# vFx-Teensy4_0.net
KiCad netlist of a schematic drawn in EAGLE
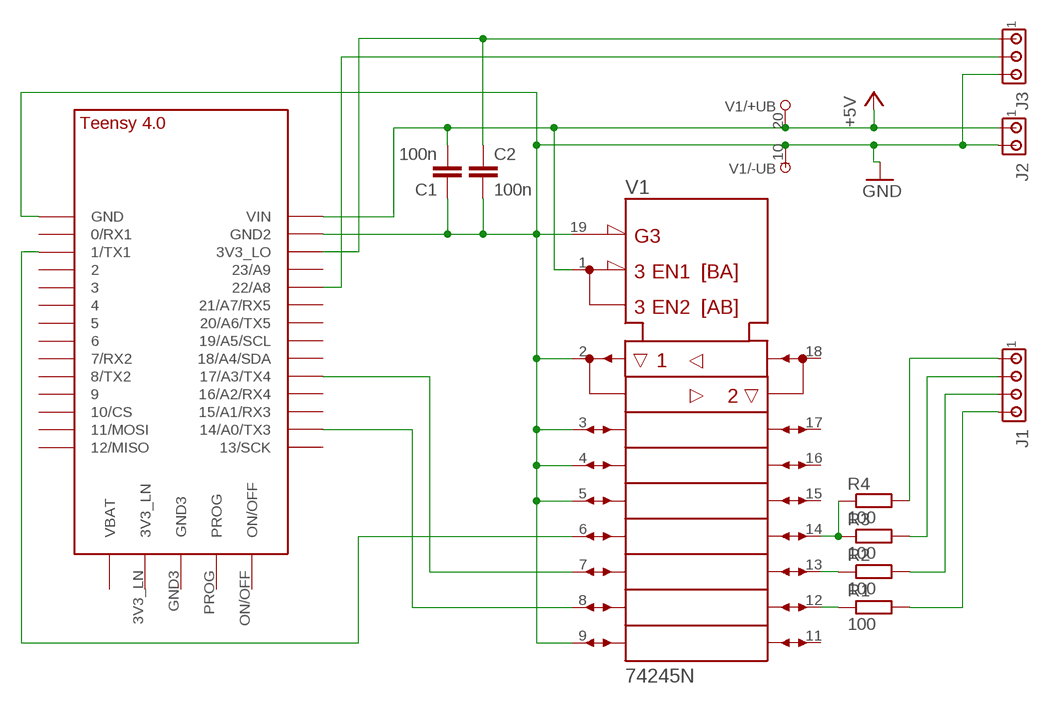
[diagram p0: schematic, sheet 1]

(export (version "E")
  (design (tool "Eeschema 10.0.6"))
  (components
    (comp (ref "C1")
      (value "100n")
      (footprint "eagle-import:C050-025X075")
      (libsource (lib "eagle-import") (part "C-EU050-025X075"))
    )
    (comp (ref "C2")
      (value "100n")
      (footprint "eagle-import:C050-025X075")
      (libsource (lib "eagle-import") (part "C-EU050-025X075"))
    )
    (comp (ref "J1")
      (value "MTA04-100")
      (footprint "eagle-import:10X04MTA")
      (libsource (lib "eagle-import") (part "MTA04-100"))
    )
    (comp (ref "J2")
      (value "MTA02-100")
      (footprint "eagle-import:10X02MTA")
      (libsource (lib "eagle-import") (part "MTA02-100"))
    )
    (comp (ref "J3")
      (value "MTA03-100")
      (footprint "eagle-import:10X03MTA")
      (libsource (lib "eagle-import") (part "MTA03-100"))
    )
    (comp (ref "R1")
      (value "100")
      (footprint "eagle-import:0207_10")
      (libsource (lib "eagle-import") (part "R-EU_0207/10"))
    )
    (comp (ref "R2")
      (value "100")
      (footprint "eagle-import:0207_10")
      (libsource (lib "eagle-import") (part "R-EU_0207/10"))
    )
    (comp (ref "R3")
      (value "100")
      (footprint "eagle-import:0207_10")
      (libsource (lib "eagle-import") (part "R-EU_0207/10"))
    )
    (comp (ref "R4")
      (value "100")
      (footprint "eagle-import:0207_10")
      (libsource (lib "eagle-import") (part "R-EU_0207/10"))
    )
    (comp (ref "U$1")
      (value "TEENSY_4.0-BASIC")
      (footprint "eagle-import:TEENSY_4.0-BASIC")
      (libsource (lib "eagle-import") (part "TEENSY_4.0-BASIC"))
    )
    (comp (ref "V1")
      (value "74245N")
      (footprint "eagle-import:DIL20")
      (libsource (lib "eagle-import") (part "74245N"))
    )
  )
  (nets
    (net (code "1") (name "+5V") (class "Default")
      (node (ref "C1") (pin "2") (pinfunction "2_2") (pintype "passive"))
      (node (ref "J2") (pin "1") (pinfunction "1_1") (pintype "passive"))
      (node (ref "U$1") (pin "VIN") (pinfunction "VIN_VIN") (pintype "bidirectional"))
      (node (ref "V1") (pin "1") (pinfunction "DIR_1") (pintype "input"))
      (node (ref "V1") (pin "20") (pinfunction "+UB_20") (pintype "power_in"))
    )
    (net (code "2") (name "GND") (class "Default")
      (node (ref "C1") (pin "1") (pinfunction "1_1") (pintype "passive"))
      (node (ref "C2") (pin "2") (pinfunction "2_2") (pintype "passive"))
      (node (ref "J2") (pin "2") (pinfunction "2_2") (pintype "passive"))
      (node (ref "J3") (pin "3") (pinfunction "3_3") (pintype "passive"))
      (node (ref "U$1") (pin "GND") (pinfunction "GND_GND") (pintype "bidirectional"))
      (node (ref "U$1") (pin "GND2") (pinfunction "GND2_GND2") (pintype "bidirectional"))
      (node (ref "V1") (pin "10") (pinfunction "-UB_10") (pintype "power_in"))
      (node (ref "V1") (pin "19") (pinfunction "~{G}_19") (pintype "input"))
      (node (ref "V1") (pin "2") (pinfunction "A1_2") (pintype "bidirectional"))
      (node (ref "V1") (pin "3") (pinfunction "A2_3") (pintype "bidirectional"))
      (node (ref "V1") (pin "4") (pinfunction "A3_4") (pintype "bidirectional"))
      (node (ref "V1") (pin "5") (pinfunction "A4_5") (pintype "bidirectional"))
      (node (ref "V1") (pin "9") (pinfunction "A8_9") (pintype "bidirectional"))
    )
    (net (code "3") (name "Net-(C2-Pad1)") (class "Default")
      (node (ref "C2") (pin "1") (pinfunction "1_1") (pintype "passive"))
      (node (ref "J3") (pin "1") (pinfunction "1_1") (pintype "passive"))
      (node (ref "U$1") (pin "3V3_LO") (pinfunction "3V3_LO_3V3_LO") (pintype "bidirectional"))
    )
    (net (code "4") (name "Net-(J1-Pad1)") (class "Default")
      (node (ref "J1") (pin "1") (pinfunction "1_1") (pintype "passive"))
      (node (ref "R4") (pin "2") (pinfunction "2_2") (pintype "passive"))
    )
    (net (code "5") (name "Net-(J1-Pad2)") (class "Default")
      (node (ref "J1") (pin "2") (pinfunction "2_2") (pintype "passive"))
      (node (ref "R3") (pin "2") (pinfunction "2_2") (pintype "passive"))
    )
    (net (code "6") (name "Net-(J1-Pad3)") (class "Default")
      (node (ref "J1") (pin "3") (pinfunction "3_3") (pintype "passive"))
      (node (ref "R2") (pin "2") (pinfunction "2_2") (pintype "passive"))
    )
    (net (code "7") (name "Net-(J1-Pad4)") (class "Default")
      (node (ref "J1") (pin "4") (pinfunction "4_4") (pintype "passive"))
      (node (ref "R1") (pin "2") (pinfunction "2_2") (pintype "passive"))
    )
    (net (code "8") (name "Net-(J3-Pad2)") (class "Default")
      (node (ref "J3") (pin "2") (pinfunction "2_2") (pintype "passive"))
      (node (ref "U$1") (pin "22/A8") (pinfunction "22/A8_22/A8") (pintype "bidirectional"))
    )
    (net (code "9") (name "Net-(U$1-1{slash}TX1)") (class "Default")
      (node (ref "U$1") (pin "1/TX") (pinfunction "1/TX1_1/TX") (pintype "bidirectional"))
      (node (ref "V1") (pin "6") (pinfunction "A5_6") (pintype "bidirectional"))
    )
    (net (code "10") (name "Net-(U$1-14{slash}A0{slash}TX3)") (class "Default")
      (node (ref "U$1") (pin "14/A0") (pinfunction "14/A0/TX3_14/A0") (pintype "bidirectional"))
      (node (ref "V1") (pin "8") (pinfunction "A7_8") (pintype "bidirectional"))
    )
    (net (code "11") (name "Net-(U$1-17{slash}A3{slash}TX4)") (class "Default")
      (node (ref "U$1") (pin "17/A3") (pinfunction "17/A3/TX4_17/A3") (pintype "bidirectional"))
      (node (ref "V1") (pin "7") (pinfunction "A6_7") (pintype "bidirectional"))
    )
    (net (code "12") (name "Net-(V1C-B5)") (class "Default")
      (node (ref "R3") (pin "1") (pinfunction "1_1") (pintype "passive"))
      (node (ref "R4") (pin "1") (pinfunction "1_1") (pintype "passive"))
      (node (ref "V1") (pin "14") (pinfunction "B5_14") (pintype "bidirectional"))
    )
    (net (code "13") (name "Net-(V1C-B6)") (class "Default")
      (node (ref "R2") (pin "1") (pinfunction "1_1") (pintype "passive"))
      (node (ref "V1") (pin "13") (pinfunction "B6_13") (pintype "bidirectional"))
    )
    (net (code "14") (name "Net-(V1C-B7)") (class "Default")
      (node (ref "R1") (pin "1") (pinfunction "1_1") (pintype "passive"))
      (node (ref "V1") (pin "12") (pinfunction "B7_12") (pintype "bidirectional"))
    )
    (net (code "15") (name "unconnected-(U$1-0{slash}RX1-Pad0{slash}RX)") (class "Default")
      (node (ref "U$1") (pin "0/RX") (pinfunction "0/RX1_0/RX") (pintype "bidirectional"))
    )
    (net (code "16") (name "unconnected-(U$1-3-Pad3{slash}CANTX)") (class "Default")
      (node (ref "U$1") (pin "3/CANTX") (pinfunction "3_3/CANTX") (pintype "bidirectional"))
    )
    (net (code "17") (name "unconnected-(U$1-4-Pad4{slash}CANRX)") (class "Default")
      (node (ref "U$1") (pin "4/CANRX") (pinfunction "4_4/CANRX") (pintype "bidirectional"))
    )
    (net (code "18") (name "unconnected-(U$1-7{slash}RX2-Pad7)") (class "Default")
      (node (ref "U$1") (pin "7") (pinfunction "7/RX2_7") (pintype "bidirectional"))
    )
    (net (code "19") (name "unconnected-(U$1-8{slash}TX2-Pad8)") (class "Default")
      (node (ref "U$1") (pin "8") (pinfunction "8/TX2_8") (pintype "bidirectional"))
    )
    (net (code "20") (name "unconnected-(U$1-9-Pad9{slash}CS)") (class "Default")
      (node (ref "U$1") (pin "9/CS") (pinfunction "9_9/CS") (pintype "bidirectional"))
    )
    (net (code "21") (name "unconnected-(U$1-15{slash}A1{slash}RX3-Pad15{slash}A1)") (class "Default")
      (node (ref "U$1") (pin "15/A1") (pinfunction "15/A1/RX3_15/A1") (pintype "bidirectional"))
    )
    (net (code "22") (name "unconnected-(U$1-16{slash}A2{slash}RX4-Pad16{slash}A2)") (class "Default")
      (node (ref "U$1") (pin "16/A2") (pinfunction "16/A2/RX4_16/A2") (pintype "bidirectional"))
    )
    (net (code "23") (name "unconnected-(U$1-20{slash}A6{slash}TX5-Pad20{slash}A6)") (class "Default")
      (node (ref "U$1") (pin "20/A6") (pinfunction "20/A6/TX5_20/A6") (pintype "bidirectional"))
    )
    (net (code "24") (name "unconnected-(U$1-21{slash}A7{slash}RX5-Pad21{slash}A7)") (class "Default")
      (node (ref "U$1") (pin "21/A7") (pinfunction "21/A7/RX5_21/A7") (pintype "bidirectional"))
    )
    (net (code "25") (name "unconnected-(U$1-Pad2)") (class "Default")
      (node (ref "U$1") (pin "2") (pinfunction "2_2") (pintype "bidirectional"))
    )
    (net (code "26") (name "unconnected-(U$1-Pad3V3_LN)") (class "Default")
      (node (ref "U$1") (pin "3V3_LN") (pinfunction "3V3_LN_3V3_LN") (pintype "bidirectional"))
    )
    (net (code "27") (name "unconnected-(U$1-Pad5)") (class "Default")
      (node (ref "U$1") (pin "5") (pinfunction "5_5") (pintype "bidirectional"))
    )
    (net (code "28") (name "unconnected-(U$1-Pad6)") (class "Default")
      (node (ref "U$1") (pin "6") (pinfunction "6_6") (pintype "bidirectional"))
    )
    (net (code "29") (name "unconnected-(U$1-Pad10{slash}CS)") (class "Default")
      (node (ref "U$1") (pin "10/CS") (pinfunction "10/CS_10/CS") (pintype "bidirectional"))
    )
    (net (code "30") (name "unconnected-(U$1-Pad11{slash}MOSI)") (class "Default")
      (node (ref "U$1") (pin "11/MOSI") (pinfunction "11/MOSI_11/MOSI") (pintype "bidirectional"))
    )
    (net (code "31") (name "unconnected-(U$1-Pad12{slash}MISO)") (class "Default")
      (node (ref "U$1") (pin "12/MISO") (pinfunction "12/MISO_12/MISO") (pintype "bidirectional"))
    )
    (net (code "32") (name "unconnected-(U$1-Pad13{slash}SCK)") (class "Default")
      (node (ref "U$1") (pin "13/SCK") (pinfunction "13/SCK_13/SCK") (pintype "bidirectional"))
    )
    (net (code "33") (name "unconnected-(U$1-Pad18{slash}A4{slash}SDA)") (class "Default")
      (node (ref "U$1") (pin "18/A4/SDA") (pinfunction "18/A4/SDA_18/A4/SDA") (pintype "bidirectional"))
    )
    (net (code "34") (name "unconnected-(U$1-Pad19{slash}A5{slash}SCL)") (class "Default")
      (node (ref "U$1") (pin "19/A5/SCL") (pinfunction "19/A5/SCL_19/A5/SCL") (pintype "bidirectional"))
    )
    (net (code "35") (name "unconnected-(U$1-Pad23{slash}A9)") (class "Default")
      (node (ref "U$1") (pin "23/A9") (pinfunction "23/A9_23/A9") (pintype "bidirectional"))
    )
    (net (code "36") (name "unconnected-(U$1-PadGND3)") (class "Default")
      (node (ref "U$1") (pin "GND3") (pinfunction "GND3_GND3") (pintype "bidirectional"))
    )
    (net (code "37") (name "unconnected-(U$1-PadON{slash}OFF)") (class "Default")
      (node (ref "U$1") (pin "ON/OFF") (pinfunction "ON/OFF_ON/OFF") (pintype "bidirectional"))
    )
    (net (code "38") (name "unconnected-(U$1-PadPROG)") (class "Default")
      (node (ref "U$1") (pin "PROG") (pinfunction "PROG_PROG") (pintype "bidirectional"))
    )
    (net (code "39") (name "unconnected-(U$1-VBAT-PadVBAT\\)") (class "Default")
      (node (ref "U$1") (pin "VBAT\\") (pinfunction "VBAT_VBAT\\") (pintype "bidirectional"))
    )
    (net (code "40") (name "unconnected-(V1C-B1-Pad18)") (class "Default")
      (node (ref "V1") (pin "18") (pinfunction "B1_18") (pintype "bidirectional"))
    )
    (net (code "41") (name "unconnected-(V1C-B2-Pad17)") (class "Default")
      (node (ref "V1") (pin "17") (pinfunction "B2_17") (pintype "bidirectional"))
    )
    (net (code "42") (name "unconnected-(V1C-B3-Pad16)") (class "Default")
      (node (ref "V1") (pin "16") (pinfunction "B3_16") (pintype "bidirectional"))
    )
    (net (code "43") (name "unconnected-(V1C-B4-Pad15)") (class "Default")
      (node (ref "V1") (pin "15") (pinfunction "B4_15") (pintype "bidirectional"))
    )
    (net (code "44") (name "unconnected-(V1C-B8-Pad11)") (class "Default")
      (node (ref "V1") (pin "11") (pinfunction "B8_11") (pintype "bidirectional"))
    )
  )
)
